# DRV8833.net
KiCad netlist of a schematic drawn in Altium Designer
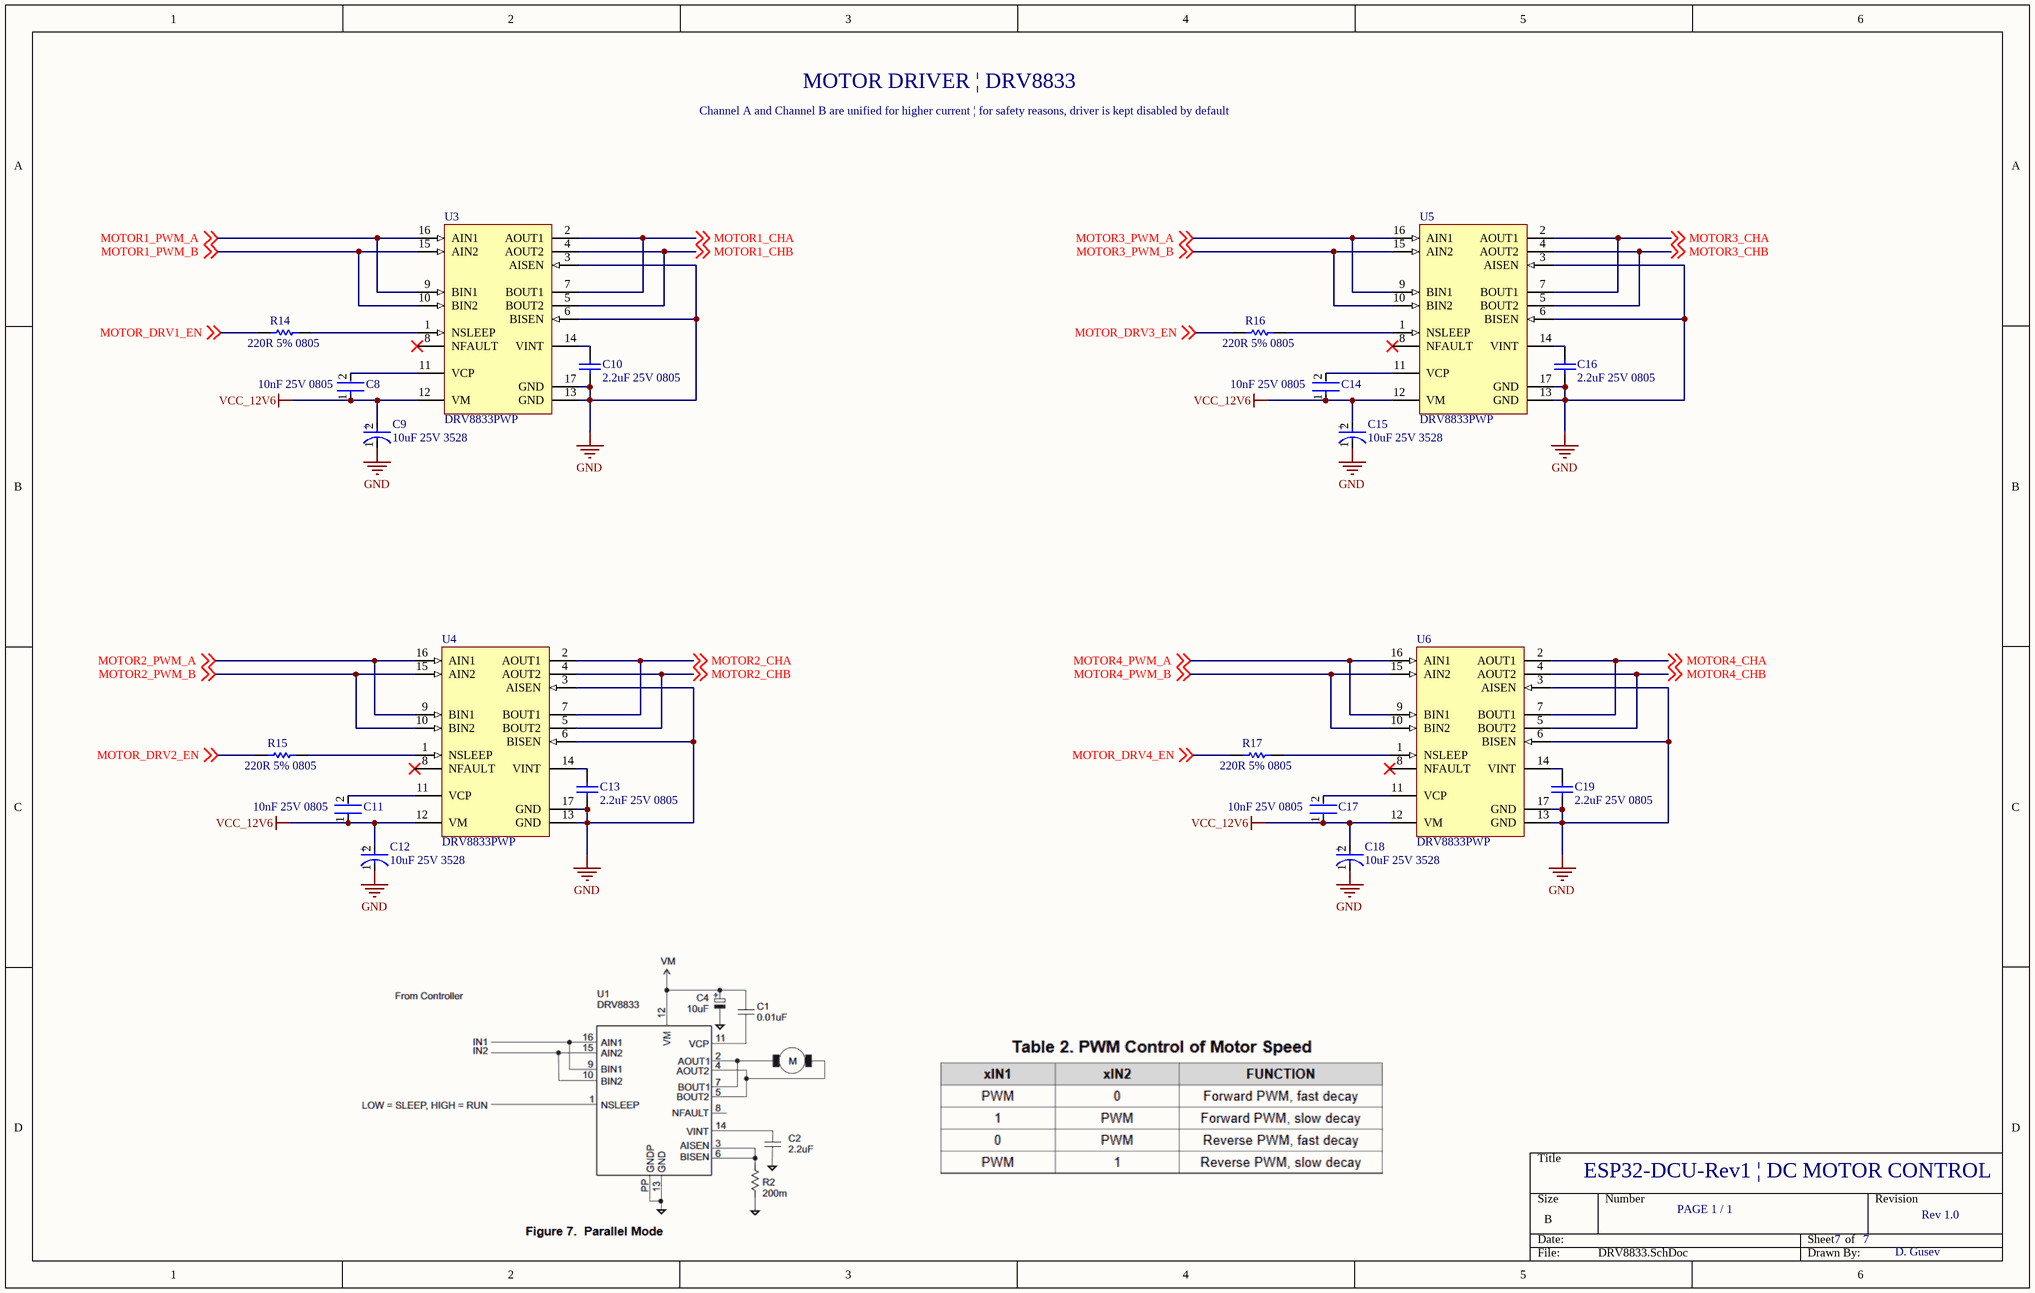
[diagram p0: DRV8833.SchDoc]

(export (version "E")
  (design (tool "Eeschema 10.0.6"))
  (components
    (comp (ref "C8")
      (value "10nF 25V 0805")
      (footprint "FP-C0805C-DN-MFG")
      (description "CAP CER 10000PF 25V 5% NP0 0805")
      (fields
        (field (name "OCTOPART") "https://octopart.com/c0805c103j3gactu-kemet-12563663")
        (field (name "TOLERANCE") "0.05")
      )
      (libsource (lib "Altium Content Vault") (part "b4654b650e69147ec39a6b967a45e02"))
    )
    (comp (ref "C9")
      (value "10uF 25V 3528")
      (footprint "FP-T491B106K025AT-MFG")
      (description "CAP TANT 10UF 10% 25V 1411")
      (fields (field (name "VOLTAGE") "25V") (field (name "TOLERANCE") "10%"))
      (libsource (lib "Altium Content Vault") (part "a00bbbee19879c290e62620ae7e47b1"))
    )
    (comp (ref "C10")
      (value "2.2uF 25V 0805")
      (footprint "CAPC2013X135X45ML10T25")
      (fields (field (name "PART NUMBER") "GRM21BF51E225ZA01L") (field (name "MANUFACTURER") "Murata"))
      (libsource (lib "Altium Content Vault") (part "CAP"))
    )
    (comp (ref "C11")
      (value "10nF 25V 0805")
      (footprint "FP-C0805C-DN-MFG")
      (description "CAP CER 10000PF 25V 5% NP0 0805")
      (fields
        (field (name "OCTOPART") "https://octopart.com/c0805c103j3gactu-kemet-12563663")
        (field (name "TOLERANCE") "0.05")
      )
      (libsource (lib "Altium Content Vault") (part "b4654b650e69147ec39a6b967a45e02"))
    )
    (comp (ref "C12")
      (value "10uF 25V 3528")
      (footprint "FP-T491B106K025AT-MFG")
      (description "CAP TANT 10UF 10% 25V 1411")
      (fields (field (name "VOLTAGE") "25V") (field (name "TOLERANCE") "10%"))
      (libsource (lib "Altium Content Vault") (part "a00bbbee19879c290e62620ae7e47b1"))
    )
    (comp (ref "C13")
      (value "2.2uF 25V 0805")
      (footprint "CAPC2013X135X45ML10T25")
      (fields (field (name "PART NUMBER") "GRM21BF51E225ZA01L") (field (name "MANUFACTURER") "Murata"))
      (libsource (lib "Altium Content Vault") (part "CAP"))
    )
    (comp (ref "C14")
      (value "10nF 25V 0805")
      (footprint "FP-C0805C-DN-MFG")
      (description "CAP CER 10000PF 25V 5% NP0 0805")
      (fields
        (field (name "OCTOPART") "https://octopart.com/c0805c103j3gactu-kemet-12563663")
        (field (name "TOLERANCE") "0.05")
      )
      (libsource (lib "Altium Content Vault") (part "b4654b650e69147ec39a6b967a45e02"))
    )
    (comp (ref "C15")
      (value "10uF 25V 3528")
      (footprint "FP-T491B106K025AT-MFG")
      (description "CAP TANT 10UF 10% 25V 1411")
      (fields (field (name "VOLTAGE") "25V") (field (name "TOLERANCE") "10%"))
      (libsource (lib "Altium Content Vault") (part "a00bbbee19879c290e62620ae7e47b1"))
    )
    (comp (ref "C16")
      (value "2.2uF 25V 0805")
      (footprint "CAPC2013X135X45ML10T25")
      (fields (field (name "PART NUMBER") "GRM21BF51E225ZA01L") (field (name "MANUFACTURER") "Murata"))
      (libsource (lib "Altium Content Vault") (part "CAP"))
    )
    (comp (ref "C17")
      (value "10nF 25V 0805")
      (footprint "FP-C0805C-DN-MFG")
      (description "CAP CER 10000PF 25V 5% NP0 0805")
      (fields
        (field (name "OCTOPART") "https://octopart.com/c0805c103j3gactu-kemet-12563663")
        (field (name "TOLERANCE") "0.05")
      )
      (libsource (lib "Altium Content Vault") (part "b4654b650e69147ec39a6b967a45e02"))
    )
    (comp (ref "C18")
      (value "10uF 25V 3528")
      (footprint "FP-T491B106K025AT-MFG")
      (description "CAP TANT 10UF 10% 25V 1411")
      (fields (field (name "VOLTAGE") "25V") (field (name "TOLERANCE") "10%"))
      (libsource (lib "Altium Content Vault") (part "a00bbbee19879c290e62620ae7e47b1"))
    )
    (comp (ref "C19")
      (value "2.2uF 25V 0805")
      (footprint "CAPC2013X135X45ML10T25")
      (fields (field (name "PART NUMBER") "GRM21BF51E225ZA01L") (field (name "MANUFACTURER") "Murata"))
      (libsource (lib "Altium Content Vault") (part "CAP"))
    )
    (comp (ref "R14")
      (value "220R 5% 0805")
      (footprint "RESC2013X60X40NL20T25")
      (fields (field (name "MANUFACTURER") "Panasonic") (field (name "PART NUMBER") "ERA6AEB221V"))
      (libsource (lib "Altium Content Vault") (part "RES"))
    )
    (comp (ref "R15")
      (value "220R 5% 0805")
      (footprint "RESC2013X60X40NL20T25")
      (fields (field (name "MANUFACTURER") "Panasonic") (field (name "PART NUMBER") "ERA6AEB221V"))
      (libsource (lib "Altium Content Vault") (part "RES"))
    )
    (comp (ref "R16")
      (value "220R 5% 0805")
      (footprint "RESC2013X60X40NL20T25")
      (fields (field (name "MANUFACTURER") "Panasonic") (field (name "PART NUMBER") "ERA6AEB221V"))
      (libsource (lib "Altium Content Vault") (part "RES"))
    )
    (comp (ref "R17")
      (value "220R 5% 0805")
      (footprint "RESC2013X60X40NL20T25")
      (fields (field (name "MANUFACTURER") "Panasonic") (field (name "PART NUMBER") "ERA6AEB221V"))
      (libsource (lib "Altium Content Vault") (part "RES"))
    )
    (comp (ref "U3")
      (value "DRV8833PWP")
      (footprint "PWP0016C_N")
      (fields (field (name "MANUFACTURER") "Texas Instruments"))
      (libsource (lib "Altium Content Vault") (part "TI-DRV8833PWP16-2370X2105TP"))
    )
    (comp (ref "U4")
      (value "DRV8833PWP")
      (footprint "PWP0016C_N")
      (fields (field (name "MANUFACTURER") "Texas Instruments"))
      (libsource (lib "Altium Content Vault") (part "TI-DRV8833PWP16-2370X2105TP"))
    )
    (comp (ref "U5")
      (value "DRV8833PWP")
      (footprint "PWP0016C_N")
      (fields (field (name "MANUFACTURER") "Texas Instruments"))
      (libsource (lib "Altium Content Vault") (part "TI-DRV8833PWP16-2370X2105TP"))
    )
    (comp (ref "U6")
      (value "DRV8833PWP")
      (footprint "PWP0016C_N")
      (fields (field (name "MANUFACTURER") "Texas Instruments"))
      (libsource (lib "Altium Content Vault") (part "TI-DRV8833PWP16-2370X2105TP"))
    )
  )
  (nets
    (net (code "1") (name "GND") (class "Default")
      (node (ref "C10") (pin "1") (pinfunction "1_1") (pintype "passive"))
      (node (ref "C12") (pin "1") (pinfunction "C_1") (pintype "passive"))
      (node (ref "C13") (pin "1") (pinfunction "1_1") (pintype "passive"))
      (node (ref "C15") (pin "1") (pinfunction "C_1") (pintype "passive"))
      (node (ref "C16") (pin "1") (pinfunction "1_1") (pintype "passive"))
      (node (ref "C18") (pin "1") (pinfunction "C_1") (pintype "passive"))
      (node (ref "C19") (pin "1") (pinfunction "1_1") (pintype "passive"))
      (node (ref "C9") (pin "1") (pinfunction "C_1") (pintype "passive"))
      (node (ref "U3") (pin "13") (pinfunction "GND_13") (pintype "power_in"))
      (node (ref "U3") (pin "17") (pinfunction "GND_17") (pintype "power_in"))
      (node (ref "U3") (pin "3") (pinfunction "AISEN_3") (pintype "input"))
      (node (ref "U3") (pin "6") (pinfunction "BISEN_6") (pintype "input"))
      (node (ref "U4") (pin "13") (pinfunction "GND_13") (pintype "power_in"))
      (node (ref "U4") (pin "17") (pinfunction "GND_17") (pintype "power_in"))
      (node (ref "U4") (pin "3") (pinfunction "AISEN_3") (pintype "input"))
      (node (ref "U4") (pin "6") (pinfunction "BISEN_6") (pintype "input"))
      (node (ref "U5") (pin "13") (pinfunction "GND_13") (pintype "power_in"))
      (node (ref "U5") (pin "17") (pinfunction "GND_17") (pintype "power_in"))
      (node (ref "U5") (pin "3") (pinfunction "AISEN_3") (pintype "input"))
      (node (ref "U5") (pin "6") (pinfunction "BISEN_6") (pintype "input"))
      (node (ref "U6") (pin "13") (pinfunction "GND_13") (pintype "power_in"))
      (node (ref "U6") (pin "17") (pinfunction "GND_17") (pintype "power_in"))
      (node (ref "U6") (pin "3") (pinfunction "AISEN_3") (pintype "input"))
      (node (ref "U6") (pin "6") (pinfunction "BISEN_6") (pintype "input"))
    )
    (net (code "2") (name "MOTOR1_CHA") (class "Default")
      (node (ref "U3") (pin "2") (pinfunction "AOUT1_2") (pintype "tri_state"))
      (node (ref "U3") (pin "7") (pinfunction "BOUT1_7") (pintype "tri_state"))
    )
    (net (code "3") (name "MOTOR1_CHB") (class "Default")
      (node (ref "U3") (pin "4") (pinfunction "AOUT2_4") (pintype "tri_state"))
      (node (ref "U3") (pin "5") (pinfunction "BOUT2_5") (pintype "tri_state"))
    )
    (net (code "4") (name "MOTOR1_PWM_A") (class "Default")
      (node (ref "U3") (pin "16") (pinfunction "AIN1_16") (pintype "input"))
      (node (ref "U3") (pin "9") (pinfunction "BIN1_9") (pintype "input"))
    )
    (net (code "5") (name "MOTOR1_PWM_B") (class "Default")
      (node (ref "U3") (pin "10") (pinfunction "BIN2_10") (pintype "input"))
      (node (ref "U3") (pin "15") (pinfunction "AIN2_15") (pintype "input"))
    )
    (net (code "6") (name "MOTOR2_CHA") (class "Default")
      (node (ref "U4") (pin "2") (pinfunction "AOUT1_2") (pintype "tri_state"))
      (node (ref "U4") (pin "7") (pinfunction "BOUT1_7") (pintype "tri_state"))
    )
    (net (code "7") (name "MOTOR2_CHB") (class "Default")
      (node (ref "U4") (pin "4") (pinfunction "AOUT2_4") (pintype "tri_state"))
      (node (ref "U4") (pin "5") (pinfunction "BOUT2_5") (pintype "tri_state"))
    )
    (net (code "8") (name "MOTOR2_PWM_A") (class "Default")
      (node (ref "U4") (pin "16") (pinfunction "AIN1_16") (pintype "input"))
      (node (ref "U4") (pin "9") (pinfunction "BIN1_9") (pintype "input"))
    )
    (net (code "9") (name "MOTOR2_PWM_B") (class "Default")
      (node (ref "U4") (pin "10") (pinfunction "BIN2_10") (pintype "input"))
      (node (ref "U4") (pin "15") (pinfunction "AIN2_15") (pintype "input"))
    )
    (net (code "10") (name "MOTOR3_CHA") (class "Default")
      (node (ref "U5") (pin "2") (pinfunction "AOUT1_2") (pintype "tri_state"))
      (node (ref "U5") (pin "7") (pinfunction "BOUT1_7") (pintype "tri_state"))
    )
    (net (code "11") (name "MOTOR3_CHB") (class "Default")
      (node (ref "U5") (pin "4") (pinfunction "AOUT2_4") (pintype "tri_state"))
      (node (ref "U5") (pin "5") (pinfunction "BOUT2_5") (pintype "tri_state"))
    )
    (net (code "12") (name "MOTOR3_PWM_A") (class "Default")
      (node (ref "U5") (pin "16") (pinfunction "AIN1_16") (pintype "input"))
      (node (ref "U5") (pin "9") (pinfunction "BIN1_9") (pintype "input"))
    )
    (net (code "13") (name "MOTOR3_PWM_B") (class "Default")
      (node (ref "U5") (pin "10") (pinfunction "BIN2_10") (pintype "input"))
      (node (ref "U5") (pin "15") (pinfunction "AIN2_15") (pintype "input"))
    )
    (net (code "14") (name "MOTOR4_CHA") (class "Default")
      (node (ref "U6") (pin "2") (pinfunction "AOUT1_2") (pintype "tri_state"))
      (node (ref "U6") (pin "7") (pinfunction "BOUT1_7") (pintype "tri_state"))
    )
    (net (code "15") (name "MOTOR4_CHB") (class "Default")
      (node (ref "U6") (pin "4") (pinfunction "AOUT2_4") (pintype "tri_state"))
      (node (ref "U6") (pin "5") (pinfunction "BOUT2_5") (pintype "tri_state"))
    )
    (net (code "16") (name "MOTOR4_PWM_A") (class "Default")
      (node (ref "U6") (pin "16") (pinfunction "AIN1_16") (pintype "input"))
      (node (ref "U6") (pin "9") (pinfunction "BIN1_9") (pintype "input"))
    )
    (net (code "17") (name "MOTOR4_PWM_B") (class "Default")
      (node (ref "U6") (pin "10") (pinfunction "BIN2_10") (pintype "input"))
      (node (ref "U6") (pin "15") (pinfunction "AIN2_15") (pintype "input"))
    )
    (net (code "18") (name "MOTOR_DRV1_EN") (class "Default")
      (node (ref "R14") (pin "1") (pinfunction "1_1") (pintype "passive"))
    )
    (net (code "19") (name "MOTOR_DRV2_EN") (class "Default")
      (node (ref "R15") (pin "1") (pinfunction "1_1") (pintype "passive"))
    )
    (net (code "20") (name "MOTOR_DRV3_EN") (class "Default")
      (node (ref "R16") (pin "1") (pinfunction "1_1") (pintype "passive"))
    )
    (net (code "21") (name "MOTOR_DRV4_EN") (class "Default")
      (node (ref "R17") (pin "1") (pinfunction "1_1") (pintype "passive"))
    )
    (net (code "22") (name "Net-(U3-NSLEEP)") (class "Default")
      (node (ref "R14") (pin "2") (pinfunction "2_2") (pintype "passive"))
      (node (ref "U3") (pin "1") (pinfunction "NSLEEP_1") (pintype "input"))
    )
    (net (code "23") (name "Net-(U3-VCP)") (class "Default")
      (node (ref "C8") (pin "2") (pinfunction "2_2") (pintype "passive"))
      (node (ref "U3") (pin "11") (pinfunction "VCP_11") (pintype "passive"))
    )
    (net (code "24") (name "Net-(U3-VINT)") (class "Default")
      (node (ref "C10") (pin "2") (pinfunction "2_2") (pintype "passive"))
      (node (ref "U3") (pin "14") (pinfunction "VINT_14") (pintype "passive"))
    )
    (net (code "25") (name "Net-(U4-NSLEEP)") (class "Default")
      (node (ref "R15") (pin "2") (pinfunction "2_2") (pintype "passive"))
      (node (ref "U4") (pin "1") (pinfunction "NSLEEP_1") (pintype "input"))
    )
    (net (code "26") (name "Net-(U4-VCP)") (class "Default")
      (node (ref "C11") (pin "2") (pinfunction "2_2") (pintype "passive"))
      (node (ref "U4") (pin "11") (pinfunction "VCP_11") (pintype "passive"))
    )
    (net (code "27") (name "Net-(U4-VINT)") (class "Default")
      (node (ref "C13") (pin "2") (pinfunction "2_2") (pintype "passive"))
      (node (ref "U4") (pin "14") (pinfunction "VINT_14") (pintype "passive"))
    )
    (net (code "28") (name "Net-(U5-NSLEEP)") (class "Default")
      (node (ref "R16") (pin "2") (pinfunction "2_2") (pintype "passive"))
      (node (ref "U5") (pin "1") (pinfunction "NSLEEP_1") (pintype "input"))
    )
    (net (code "29") (name "Net-(U5-VCP)") (class "Default")
      (node (ref "C14") (pin "2") (pinfunction "2_2") (pintype "passive"))
      (node (ref "U5") (pin "11") (pinfunction "VCP_11") (pintype "passive"))
    )
    (net (code "30") (name "Net-(U5-VINT)") (class "Default")
      (node (ref "C16") (pin "2") (pinfunction "2_2") (pintype "passive"))
      (node (ref "U5") (pin "14") (pinfunction "VINT_14") (pintype "passive"))
    )
    (net (code "31") (name "Net-(U6-NSLEEP)") (class "Default")
      (node (ref "R17") (pin "2") (pinfunction "2_2") (pintype "passive"))
      (node (ref "U6") (pin "1") (pinfunction "NSLEEP_1") (pintype "input"))
    )
    (net (code "32") (name "Net-(U6-VCP)") (class "Default")
      (node (ref "C17") (pin "2") (pinfunction "2_2") (pintype "passive"))
      (node (ref "U6") (pin "11") (pinfunction "VCP_11") (pintype "passive"))
    )
    (net (code "33") (name "Net-(U6-VINT)") (class "Default")
      (node (ref "C19") (pin "2") (pinfunction "2_2") (pintype "passive"))
      (node (ref "U6") (pin "14") (pinfunction "VINT_14") (pintype "passive"))
    )
    (net (code "34") (name "VCC_12V6") (class "Default")
      (node (ref "C11") (pin "1") (pinfunction "1_1") (pintype "passive"))
      (node (ref "C12") (pin "2") (pinfunction "A_2") (pintype "passive"))
      (node (ref "C14") (pin "1") (pinfunction "1_1") (pintype "passive"))
      (node (ref "C15") (pin "2") (pinfunction "A_2") (pintype "passive"))
      (node (ref "C17") (pin "1") (pinfunction "1_1") (pintype "passive"))
      (node (ref "C18") (pin "2") (pinfunction "A_2") (pintype "passive"))
      (node (ref "C8") (pin "1") (pinfunction "1_1") (pintype "passive"))
      (node (ref "C9") (pin "2") (pinfunction "A_2") (pintype "passive"))
      (node (ref "U3") (pin "12") (pinfunction "VM_12") (pintype "power_in"))
      (node (ref "U4") (pin "12") (pinfunction "VM_12") (pintype "power_in"))
      (node (ref "U5") (pin "12") (pinfunction "VM_12") (pintype "power_in"))
      (node (ref "U6") (pin "12") (pinfunction "VM_12") (pintype "power_in"))
    )
    (net (code "35") (name "unconnected-(U3-NFAULT-Pad8)") (class "Default")
      (node (ref "U3") (pin "8") (pinfunction "NFAULT_8") (pintype "open_collector+no_connect"))
    )
    (net (code "36") (name "unconnected-(U4-NFAULT-Pad8)") (class "Default")
      (node (ref "U4") (pin "8") (pinfunction "NFAULT_8") (pintype "open_collector+no_connect"))
    )
    (net (code "37") (name "unconnected-(U5-NFAULT-Pad8)") (class "Default")
      (node (ref "U5") (pin "8") (pinfunction "NFAULT_8") (pintype "open_collector+no_connect"))
    )
    (net (code "38") (name "unconnected-(U6-NFAULT-Pad8)") (class "Default")
      (node (ref "U6") (pin "8") (pinfunction "NFAULT_8") (pintype "open_collector+no_connect"))
    )
  )
)
